# Strain_Gauge_Amplifiers.net
KiCad netlist of a schematic drawn in Altium Designer
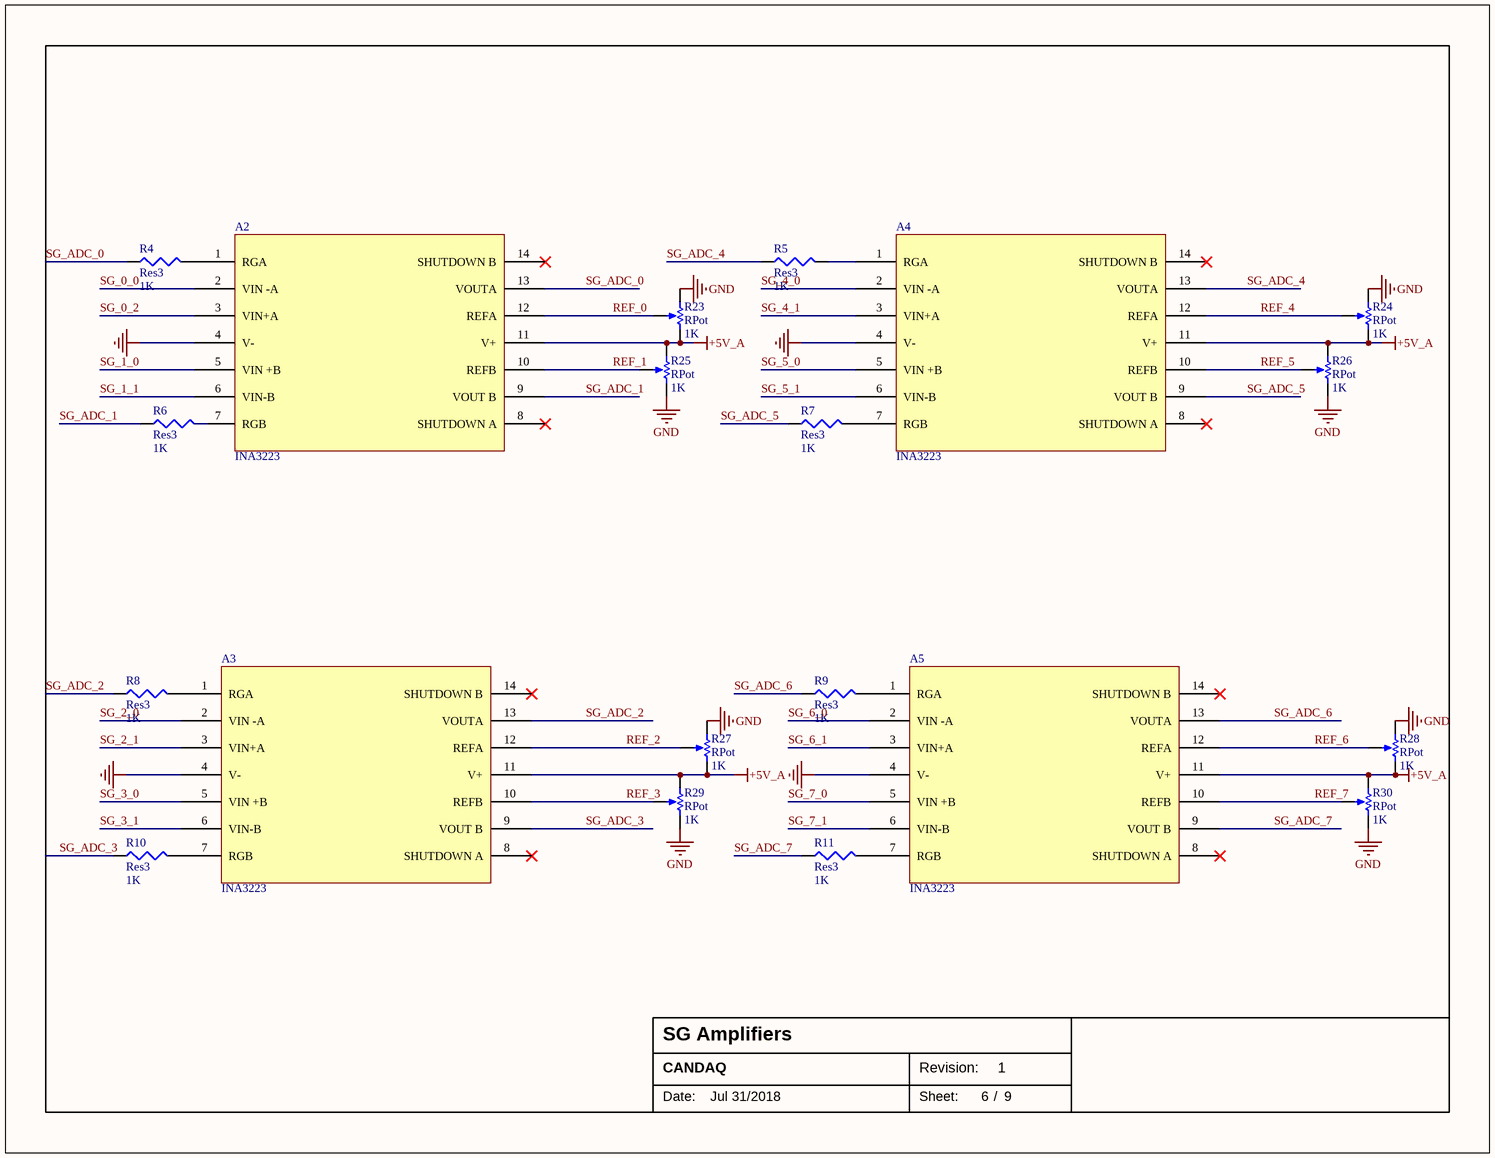
[diagram p0: Strain Gauge Amplifiers.SchDoc]

(export (version "E")
  (design (tool "Eeschema 10.0.6"))
  (components
    (comp (ref "A2") (value "INA3223") (footprint "TSSOP-14") (libsource (lib "CANDAQ") (part "INA3223")))
    (comp (ref "A3") (value "INA3223") (footprint "TSSOP-14") (libsource (lib "CANDAQ") (part "INA3223")))
    (comp (ref "A4") (value "INA3223") (footprint "TSSOP-14") (libsource (lib "CANDAQ") (part "INA3223")))
    (comp (ref "A5") (value "INA3223") (footprint "TSSOP-14") (libsource (lib "CANDAQ") (part "INA3223")))
    (comp (ref "R4")
      (value "Res3")
      (footprint "1206")
      (description "Resistor")
      (fields (field (name "ALTIUM_VALUE") "1K") (field (name "PUBLISHER") "Altium Limited"))
      (libsource (lib "Miscellaneous Devices") (part "Res3"))
    )
    (comp (ref "R5")
      (value "Res3")
      (footprint "1206")
      (description "Resistor")
      (fields (field (name "ALTIUM_VALUE") "1K") (field (name "PUBLISHER") "Altium Limited"))
      (libsource (lib "Miscellaneous Devices") (part "Res3"))
    )
    (comp (ref "R6")
      (value "Res3")
      (footprint "1206")
      (description "Resistor")
      (fields (field (name "ALTIUM_VALUE") "1K") (field (name "PUBLISHER") "Altium Limited"))
      (libsource (lib "Miscellaneous Devices") (part "Res3"))
    )
    (comp (ref "R7")
      (value "Res3")
      (footprint "1206")
      (description "Resistor")
      (fields (field (name "ALTIUM_VALUE") "1K") (field (name "PUBLISHER") "Altium Limited"))
      (libsource (lib "Miscellaneous Devices") (part "Res3"))
    )
    (comp (ref "R8")
      (value "Res3")
      (footprint "1206")
      (description "Resistor")
      (fields (field (name "ALTIUM_VALUE") "1K") (field (name "PUBLISHER") "Altium Limited"))
      (libsource (lib "Miscellaneous Devices") (part "Res3"))
    )
    (comp (ref "R9")
      (value "Res3")
      (footprint "1206")
      (description "Resistor")
      (fields (field (name "ALTIUM_VALUE") "1K") (field (name "PUBLISHER") "Altium Limited"))
      (libsource (lib "Miscellaneous Devices") (part "Res3"))
    )
    (comp (ref "R10")
      (value "Res3")
      (footprint "1206")
      (description "Resistor")
      (fields (field (name "ALTIUM_VALUE") "1K") (field (name "PUBLISHER") "Altium Limited"))
      (libsource (lib "Miscellaneous Devices") (part "Res3"))
    )
    (comp (ref "R11")
      (value "Res3")
      (footprint "1206")
      (description "Resistor")
      (fields (field (name "ALTIUM_VALUE") "1K") (field (name "PUBLISHER") "Altium Limited"))
      (libsource (lib "Miscellaneous Devices") (part "Res3"))
    )
    (comp (ref "R23")
      (value "RPot")
      (footprint "POT")
      (description "Potentiometer")
      (fields (field (name "ALTIUM_VALUE") "1K") (field (name "PUBLISHER") "Altium Limited"))
      (libsource (lib "Miscellaneous Devices") (part "RPot"))
    )
    (comp (ref "R24")
      (value "RPot")
      (footprint "POT")
      (description "Potentiometer")
      (fields (field (name "ALTIUM_VALUE") "1K") (field (name "PUBLISHER") "Altium Limited"))
      (libsource (lib "Miscellaneous Devices") (part "RPot"))
    )
    (comp (ref "R25")
      (value "RPot")
      (footprint "POT")
      (description "Potentiometer")
      (fields (field (name "ALTIUM_VALUE") "1K") (field (name "PUBLISHER") "Altium Limited"))
      (libsource (lib "Miscellaneous Devices") (part "RPot"))
    )
    (comp (ref "R26")
      (value "RPot")
      (footprint "POT")
      (description "Potentiometer")
      (fields (field (name "ALTIUM_VALUE") "1K") (field (name "PUBLISHER") "Altium Limited"))
      (libsource (lib "Miscellaneous Devices") (part "RPot"))
    )
    (comp (ref "R27")
      (value "RPot")
      (footprint "POT")
      (description "Potentiometer")
      (fields (field (name "ALTIUM_VALUE") "1K") (field (name "PUBLISHER") "Altium Limited"))
      (libsource (lib "Miscellaneous Devices") (part "RPot"))
    )
    (comp (ref "R28")
      (value "RPot")
      (footprint "POT")
      (description "Potentiometer")
      (fields (field (name "ALTIUM_VALUE") "1K") (field (name "PUBLISHER") "Altium Limited"))
      (libsource (lib "Miscellaneous Devices") (part "RPot"))
    )
    (comp (ref "R29")
      (value "RPot")
      (footprint "POT")
      (description "Potentiometer")
      (fields (field (name "ALTIUM_VALUE") "1K") (field (name "PUBLISHER") "Altium Limited"))
      (libsource (lib "Miscellaneous Devices") (part "RPot"))
    )
    (comp (ref "R30")
      (value "RPot")
      (footprint "POT")
      (description "Potentiometer")
      (fields (field (name "ALTIUM_VALUE") "1K") (field (name "PUBLISHER") "Altium Limited"))
      (libsource (lib "Miscellaneous Devices") (part "RPot"))
    )
  )
  (nets
    (net (code "1") (name "+5V_A") (class "Default")
      (node (ref "A2") (pin "11") (pinfunction "V+_11") (pintype "passive"))
      (node (ref "A3") (pin "11") (pinfunction "V+_11") (pintype "passive"))
      (node (ref "A4") (pin "11") (pinfunction "V+_11") (pintype "passive"))
      (node (ref "A5") (pin "11") (pinfunction "V+_11") (pintype "passive"))
      (node (ref "R23") (pin "2") (pinfunction "BOT_2") (pintype "passive"))
      (node (ref "R24") (pin "2") (pinfunction "BOT_2") (pintype "passive"))
      (node (ref "R25") (pin "1") (pinfunction "TOP_1") (pintype "passive"))
      (node (ref "R26") (pin "1") (pinfunction "TOP_1") (pintype "passive"))
      (node (ref "R27") (pin "2") (pinfunction "BOT_2") (pintype "passive"))
      (node (ref "R28") (pin "2") (pinfunction "BOT_2") (pintype "passive"))
      (node (ref "R29") (pin "1") (pinfunction "TOP_1") (pintype "passive"))
      (node (ref "R30") (pin "1") (pinfunction "TOP_1") (pintype "passive"))
    )
    (net (code "2") (name "/REF_0") (class "Default")
      (node (ref "A2") (pin "12") (pinfunction "REFA_12") (pintype "passive"))
      (node (ref "R23") (pin "3") (pinfunction "TAP_3") (pintype "passive"))
    )
    (net (code "3") (name "/REF_1") (class "Default")
      (node (ref "A2") (pin "10") (pinfunction "REFB_10") (pintype "passive"))
      (node (ref "R25") (pin "3") (pinfunction "TAP_3") (pintype "passive"))
    )
    (net (code "4") (name "/REF_2") (class "Default")
      (node (ref "A3") (pin "12") (pinfunction "REFA_12") (pintype "passive"))
      (node (ref "R27") (pin "3") (pinfunction "TAP_3") (pintype "passive"))
    )
    (net (code "5") (name "/REF_3") (class "Default")
      (node (ref "A3") (pin "10") (pinfunction "REFB_10") (pintype "passive"))
      (node (ref "R29") (pin "3") (pinfunction "TAP_3") (pintype "passive"))
    )
    (net (code "6") (name "/REF_4") (class "Default")
      (node (ref "A4") (pin "12") (pinfunction "REFA_12") (pintype "passive"))
      (node (ref "R24") (pin "3") (pinfunction "TAP_3") (pintype "passive"))
    )
    (net (code "7") (name "/REF_5") (class "Default")
      (node (ref "A4") (pin "10") (pinfunction "REFB_10") (pintype "passive"))
      (node (ref "R26") (pin "3") (pinfunction "TAP_3") (pintype "passive"))
    )
    (net (code "8") (name "/REF_6") (class "Default")
      (node (ref "A5") (pin "12") (pinfunction "REFA_12") (pintype "passive"))
      (node (ref "R28") (pin "3") (pinfunction "TAP_3") (pintype "passive"))
    )
    (net (code "9") (name "/REF_7") (class "Default")
      (node (ref "A5") (pin "10") (pinfunction "REFB_10") (pintype "passive"))
      (node (ref "R30") (pin "3") (pinfunction "TAP_3") (pintype "passive"))
    )
    (net (code "10") (name "/SG_0_0") (class "Default")
      (node (ref "A2") (pin "2") (pinfunction "VIN_-A_2") (pintype "passive"))
    )
    (net (code "11") (name "/SG_0_2") (class "Default")
      (node (ref "A2") (pin "3") (pinfunction "VIN+A_3") (pintype "passive"))
    )
    (net (code "12") (name "/SG_1_0") (class "Default")
      (node (ref "A2") (pin "5") (pinfunction "VIN_+B_5") (pintype "passive"))
    )
    (net (code "13") (name "/SG_1_1") (class "Default")
      (node (ref "A2") (pin "6") (pinfunction "VIN-B_6") (pintype "passive"))
    )
    (net (code "14") (name "/SG_2_0") (class "Default")
      (node (ref "A3") (pin "2") (pinfunction "VIN_-A_2") (pintype "passive"))
    )
    (net (code "15") (name "/SG_2_1") (class "Default")
      (node (ref "A3") (pin "3") (pinfunction "VIN+A_3") (pintype "passive"))
    )
    (net (code "16") (name "/SG_3_0") (class "Default")
      (node (ref "A3") (pin "5") (pinfunction "VIN_+B_5") (pintype "passive"))
    )
    (net (code "17") (name "/SG_3_1") (class "Default")
      (node (ref "A3") (pin "6") (pinfunction "VIN-B_6") (pintype "passive"))
    )
    (net (code "18") (name "/SG_4_0") (class "Default")
      (node (ref "A4") (pin "2") (pinfunction "VIN_-A_2") (pintype "passive"))
    )
    (net (code "19") (name "/SG_4_1") (class "Default")
      (node (ref "A4") (pin "3") (pinfunction "VIN+A_3") (pintype "passive"))
    )
    (net (code "20") (name "/SG_5_0") (class "Default")
      (node (ref "A4") (pin "5") (pinfunction "VIN_+B_5") (pintype "passive"))
    )
    (net (code "21") (name "/SG_5_1") (class "Default")
      (node (ref "A4") (pin "6") (pinfunction "VIN-B_6") (pintype "passive"))
    )
    (net (code "22") (name "/SG_6_0") (class "Default")
      (node (ref "A5") (pin "2") (pinfunction "VIN_-A_2") (pintype "passive"))
    )
    (net (code "23") (name "/SG_6_1") (class "Default")
      (node (ref "A5") (pin "3") (pinfunction "VIN+A_3") (pintype "passive"))
    )
    (net (code "24") (name "/SG_7_0") (class "Default")
      (node (ref "A5") (pin "5") (pinfunction "VIN_+B_5") (pintype "passive"))
    )
    (net (code "25") (name "/SG_7_1") (class "Default")
      (node (ref "A5") (pin "6") (pinfunction "VIN-B_6") (pintype "passive"))
    )
    (net (code "26") (name "/SG_ADC_0") (class "Default")
      (node (ref "A2") (pin "13") (pinfunction "VOUTA_13") (pintype "passive"))
      (node (ref "R4") (pin "1") (pinfunction "1_1") (pintype "passive"))
    )
    (net (code "27") (name "/SG_ADC_1") (class "Default")
      (node (ref "A2") (pin "9") (pinfunction "VOUT_B_9") (pintype "passive"))
      (node (ref "R6") (pin "1") (pinfunction "1_1") (pintype "passive"))
    )
    (net (code "28") (name "/SG_ADC_2") (class "Default")
      (node (ref "A3") (pin "13") (pinfunction "VOUTA_13") (pintype "passive"))
      (node (ref "R8") (pin "1") (pinfunction "1_1") (pintype "passive"))
    )
    (net (code "29") (name "/SG_ADC_3") (class "Default")
      (node (ref "A3") (pin "9") (pinfunction "VOUT_B_9") (pintype "passive"))
      (node (ref "R10") (pin "1") (pinfunction "1_1") (pintype "passive"))
    )
    (net (code "30") (name "/SG_ADC_4") (class "Default")
      (node (ref "A4") (pin "13") (pinfunction "VOUTA_13") (pintype "passive"))
      (node (ref "R5") (pin "1") (pinfunction "1_1") (pintype "passive"))
    )
    (net (code "31") (name "/SG_ADC_5") (class "Default")
      (node (ref "A4") (pin "9") (pinfunction "VOUT_B_9") (pintype "passive"))
      (node (ref "R7") (pin "1") (pinfunction "1_1") (pintype "passive"))
    )
    (net (code "32") (name "/SG_ADC_6") (class "Default")
      (node (ref "A5") (pin "13") (pinfunction "VOUTA_13") (pintype "passive"))
      (node (ref "R9") (pin "1") (pinfunction "1_1") (pintype "passive"))
    )
    (net (code "33") (name "/SG_ADC_7") (class "Default")
      (node (ref "A5") (pin "9") (pinfunction "VOUT_B_9") (pintype "passive"))
      (node (ref "R11") (pin "1") (pinfunction "1_1") (pintype "passive"))
    )
    (net (code "34") (name "GND") (class "Default")
      (node (ref "A2") (pin "4") (pinfunction "V-_4") (pintype "passive"))
      (node (ref "A3") (pin "4") (pinfunction "V-_4") (pintype "passive"))
      (node (ref "A4") (pin "4") (pinfunction "V-_4") (pintype "passive"))
      (node (ref "A5") (pin "4") (pinfunction "V-_4") (pintype "passive"))
      (node (ref "R23") (pin "1") (pinfunction "TOP_1") (pintype "passive"))
      (node (ref "R24") (pin "1") (pinfunction "TOP_1") (pintype "passive"))
      (node (ref "R25") (pin "2") (pinfunction "BOT_2") (pintype "passive"))
      (node (ref "R26") (pin "2") (pinfunction "BOT_2") (pintype "passive"))
      (node (ref "R27") (pin "1") (pinfunction "TOP_1") (pintype "passive"))
      (node (ref "R28") (pin "1") (pinfunction "TOP_1") (pintype "passive"))
      (node (ref "R29") (pin "2") (pinfunction "BOT_2") (pintype "passive"))
      (node (ref "R30") (pin "2") (pinfunction "BOT_2") (pintype "passive"))
    )
    (net (code "35") (name "Net-(A2-RGA)") (class "Default")
      (node (ref "A2") (pin "1") (pinfunction "RGA_1") (pintype "passive"))
      (node (ref "R4") (pin "2") (pinfunction "2_2") (pintype "passive"))
    )
    (net (code "36") (name "Net-(A2-RGB)") (class "Default")
      (node (ref "A2") (pin "7") (pinfunction "RGB_7") (pintype "passive"))
      (node (ref "R6") (pin "2") (pinfunction "2_2") (pintype "passive"))
    )
    (net (code "37") (name "Net-(A3-RGA)") (class "Default")
      (node (ref "A3") (pin "1") (pinfunction "RGA_1") (pintype "passive"))
      (node (ref "R8") (pin "2") (pinfunction "2_2") (pintype "passive"))
    )
    (net (code "38") (name "Net-(A3-RGB)") (class "Default")
      (node (ref "A3") (pin "7") (pinfunction "RGB_7") (pintype "passive"))
      (node (ref "R10") (pin "2") (pinfunction "2_2") (pintype "passive"))
    )
    (net (code "39") (name "Net-(A4-RGA)") (class "Default")
      (node (ref "A4") (pin "1") (pinfunction "RGA_1") (pintype "passive"))
      (node (ref "R5") (pin "2") (pinfunction "2_2") (pintype "passive"))
    )
    (net (code "40") (name "Net-(A4-RGB)") (class "Default")
      (node (ref "A4") (pin "7") (pinfunction "RGB_7") (pintype "passive"))
      (node (ref "R7") (pin "2") (pinfunction "2_2") (pintype "passive"))
    )
    (net (code "41") (name "Net-(A5-RGA)") (class "Default")
      (node (ref "A5") (pin "1") (pinfunction "RGA_1") (pintype "passive"))
      (node (ref "R9") (pin "2") (pinfunction "2_2") (pintype "passive"))
    )
    (net (code "42") (name "Net-(A5-RGB)") (class "Default")
      (node (ref "A5") (pin "7") (pinfunction "RGB_7") (pintype "passive"))
      (node (ref "R11") (pin "2") (pinfunction "2_2") (pintype "passive"))
    )
    (net (code "43") (name "unconnected-(A2-SHUTDOWN_A-Pad8)") (class "Default")
      (node (ref "A2") (pin "8") (pinfunction "SHUTDOWN_A_8") (pintype "passive+no_connect"))
    )
    (net (code "44") (name "unconnected-(A2-SHUTDOWN_B-Pad14)") (class "Default")
      (node (ref "A2") (pin "14") (pinfunction "SHUTDOWN_B_14") (pintype "passive+no_connect"))
    )
    (net (code "45") (name "unconnected-(A3-SHUTDOWN_A-Pad8)") (class "Default")
      (node (ref "A3") (pin "8") (pinfunction "SHUTDOWN_A_8") (pintype "passive+no_connect"))
    )
    (net (code "46") (name "unconnected-(A3-SHUTDOWN_B-Pad14)") (class "Default")
      (node (ref "A3") (pin "14") (pinfunction "SHUTDOWN_B_14") (pintype "passive+no_connect"))
    )
    (net (code "47") (name "unconnected-(A4-SHUTDOWN_A-Pad8)") (class "Default")
      (node (ref "A4") (pin "8") (pinfunction "SHUTDOWN_A_8") (pintype "passive+no_connect"))
    )
    (net (code "48") (name "unconnected-(A4-SHUTDOWN_B-Pad14)") (class "Default")
      (node (ref "A4") (pin "14") (pinfunction "SHUTDOWN_B_14") (pintype "passive+no_connect"))
    )
    (net (code "49") (name "unconnected-(A5-SHUTDOWN_A-Pad8)") (class "Default")
      (node (ref "A5") (pin "8") (pinfunction "SHUTDOWN_A_8") (pintype "passive+no_connect"))
    )
    (net (code "50") (name "unconnected-(A5-SHUTDOWN_B-Pad14)") (class "Default")
      (node (ref "A5") (pin "14") (pinfunction "SHUTDOWN_B_14") (pintype "passive+no_connect"))
    )
  )
)
